# bldcshield.net
KiCad netlist of a schematic drawn in EAGLE
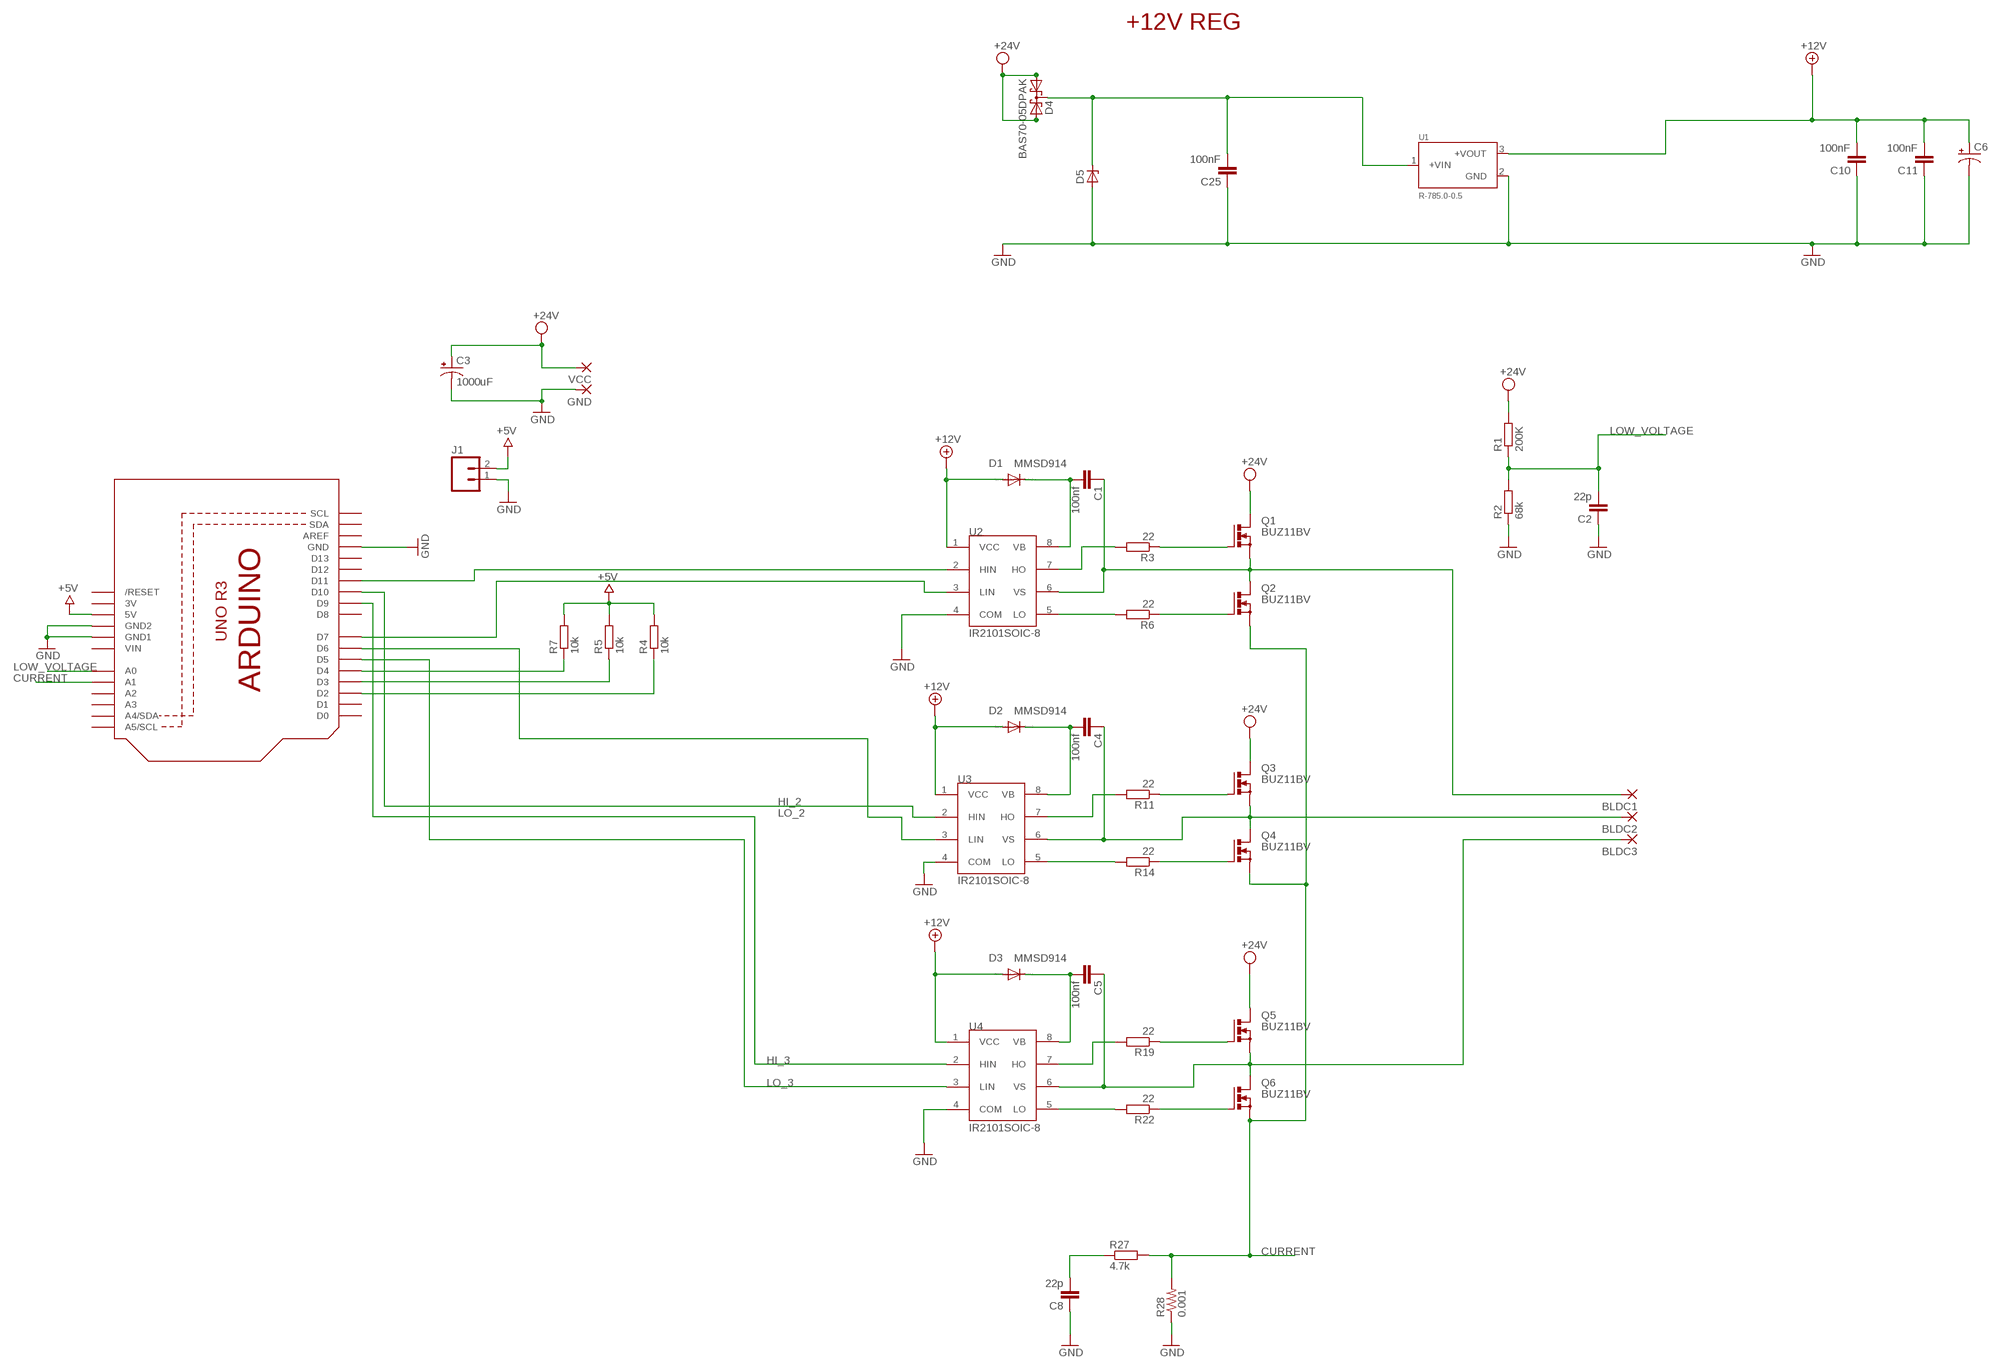
[diagram p0: schematic, sheet 1]

(export (version "E")
  (design (tool "Eeschema 10.0.6"))
  (components
    (comp (ref "BLDC1")
      (value "WIREPAD4,16O1,6")
      (footprint "eagle-import:4,16O1,6")
      (libsource (lib "eagle-import") (part "WIREPAD4,16O1,6"))
    )
    (comp (ref "BLDC2")
      (value "WIREPAD4,16O1,6")
      (footprint "eagle-import:4,16O1,6")
      (libsource (lib "eagle-import") (part "WIREPAD4,16O1,6"))
    )
    (comp (ref "BLDC3")
      (value "WIREPAD4,16O1,6")
      (footprint "eagle-import:4,16O1,6")
      (libsource (lib "eagle-import") (part "WIREPAD4,16O1,6"))
    )
    (comp (ref "C1")
      (value "100nf")
      (footprint "eagle-import:C1206")
      (libsource (lib "eagle-import") (part "C-EUC1206"))
    )
    (comp (ref "C2")
      (value "22p")
      (footprint "eagle-import:C1206")
      (libsource (lib "eagle-import") (part "C-EUC1206"))
    )
    (comp (ref "C3")
      (value "1000uF")
      (footprint "eagle-import:CPOL-RADIAL-1000UF-63V")
      (libsource (lib "eagle-import") (part "SparkFun-Passives_CAP_POLPTH3"))
    )
    (comp (ref "C4")
      (value "100nf")
      (footprint "eagle-import:C1206")
      (libsource (lib "eagle-import") (part "C-EUC1206"))
    )
    (comp (ref "C5")
      (value "100nf")
      (footprint "eagle-import:C1206")
      (libsource (lib "eagle-import") (part "C-EUC1206"))
    )
    (comp (ref "C6")
      (value "CAP_POLPTH1")
      (footprint "eagle-import:CPOL-RADIAL-100UF-25V")
      (libsource (lib "eagle-import") (part "CAP_POLPTH1"))
    )
    (comp (ref "C8")
      (value "22p")
      (footprint "eagle-import:C1206")
      (libsource (lib "eagle-import") (part "C-EUC1206"))
    )
    (comp (ref "C10")
      (value "100nF")
      (footprint "eagle-import:C1206")
      (libsource (lib "eagle-import") (part "C-EUC1206"))
    )
    (comp (ref "C11")
      (value "100nF")
      (footprint "eagle-import:C1206")
      (libsource (lib "eagle-import") (part "C-EUC1206"))
    )
    (comp (ref "C25")
      (value "100nF")
      (footprint "eagle-import:C1206")
      (libsource (lib "eagle-import") (part "C-EUC1206"))
    )
    (comp (ref "D1")
      (value "MMSD914")
      (footprint "eagle-import:SOD123")
      (libsource (lib "eagle-import") (part "DIODE-SOD123"))
    )
    (comp (ref "D2")
      (value "MMSD914")
      (footprint "eagle-import:SOD123")
      (libsource (lib "eagle-import") (part "DIODE-SOD123"))
    )
    (comp (ref "D3")
      (value "MMSD914")
      (footprint "eagle-import:SOD123")
      (libsource (lib "eagle-import") (part "DIODE-SOD123"))
    )
    (comp (ref "D4")
      (value "BAS70-05DPAK")
      (footprint "eagle-import:DPAK229P990X238-3N")
      (libsource (lib "eagle-import") (part "BAS70-05DPAK"))
    )
    (comp (ref "D5")
      (value "SMF43A")
      (footprint "eagle-import:SOD123F")
      (fields (field (name "MF") "Littelfuse"))
      (libsource (lib "eagle-import") (part "SMFA43"))
    )
    (comp (ref "GND")
      (value "WIREPAD4,16O1,6")
      (footprint "eagle-import:4,16O1,6")
      (libsource (lib "eagle-import") (part "WIREPAD4,16O1,6"))
    )
    (comp (ref "J1")
      (value "M02PTH")
      (footprint "eagle-import:1X02")
      (libsource (lib "eagle-import") (part "M02PTH"))
    )
    (comp (ref "Q1")
      (value "BUZ11BV")
      (footprint "eagle-import:TO220BV")
      (libsource (lib "eagle-import") (part "BUZ11BV"))
    )
    (comp (ref "Q2")
      (value "BUZ11BV")
      (footprint "eagle-import:TO220BV")
      (libsource (lib "eagle-import") (part "BUZ11BV"))
    )
    (comp (ref "Q3")
      (value "BUZ11BV")
      (footprint "eagle-import:TO220BV")
      (libsource (lib "eagle-import") (part "BUZ11BV"))
    )
    (comp (ref "Q4")
      (value "BUZ11BV")
      (footprint "eagle-import:TO220BV")
      (libsource (lib "eagle-import") (part "BUZ11BV"))
    )
    (comp (ref "Q5")
      (value "BUZ11BV")
      (footprint "eagle-import:TO220BV")
      (libsource (lib "eagle-import") (part "BUZ11BV"))
    )
    (comp (ref "Q6")
      (value "BUZ11BV")
      (footprint "eagle-import:TO220BV")
      (libsource (lib "eagle-import") (part "BUZ11BV"))
    )
    (comp (ref "Q8")
      (value "Shield")
      (footprint "eagle-import:ARDUINOR3-NOTEXT-NOIOREF")
      (libsource (lib "eagle-import") (part "ARDUINOR3-NOIOREF-NOTEXT"))
    )
    (comp (ref "R1")
      (value "200K")
      (footprint "eagle-import:R1206")
      (libsource (lib "eagle-import") (part "R-EU_R1206"))
    )
    (comp (ref "R2")
      (value "68k")
      (footprint "eagle-import:R1206")
      (libsource (lib "eagle-import") (part "R-EU_R1206"))
    )
    (comp (ref "R3")
      (value "22")
      (footprint "eagle-import:R1206")
      (libsource (lib "eagle-import") (part "R-EU_R1206"))
    )
    (comp (ref "R4")
      (value "10k")
      (footprint "eagle-import:R1206")
      (libsource (lib "eagle-import") (part "R-EU_R1206"))
    )
    (comp (ref "R5")
      (value "10k")
      (footprint "eagle-import:R1206")
      (libsource (lib "eagle-import") (part "R-EU_R1206"))
    )
    (comp (ref "R6")
      (value "22")
      (footprint "eagle-import:R1206")
      (libsource (lib "eagle-import") (part "R-EU_R1206"))
    )
    (comp (ref "R7")
      (value "10k")
      (footprint "eagle-import:R1206")
      (libsource (lib "eagle-import") (part "R-EU_R1206"))
    )
    (comp (ref "R11")
      (value "22")
      (footprint "eagle-import:R1206")
      (libsource (lib "eagle-import") (part "R-EU_R1206"))
    )
    (comp (ref "R14")
      (value "22")
      (footprint "eagle-import:R1206")
      (libsource (lib "eagle-import") (part "R-EU_R1206"))
    )
    (comp (ref "R19")
      (value "22")
      (footprint "eagle-import:R1206")
      (libsource (lib "eagle-import") (part "R-EU_R1206"))
    )
    (comp (ref "R22")
      (value "22")
      (footprint "eagle-import:R1206")
      (libsource (lib "eagle-import") (part "R-EU_R1206"))
    )
    (comp (ref "R27")
      (value "4.7k")
      (footprint "eagle-import:R1206")
      (libsource (lib "eagle-import") (part "R-EU_R1206"))
    )
    (comp (ref "R28")
      (value "0.001")
      (footprint "eagle-import:R2512")
      (libsource (lib "eagle-import") (part "R-US_R2512"))
    )
    (comp (ref "U1")
      (value "R-785.0-0.5")
      (footprint "eagle-import:RECOM_R-785.0-0.5")
      (fields (field (name "MF") "Recom Power"))
      (libsource (lib "eagle-import") (part "R-785.0-0.5"))
    )
    (comp (ref "U2")
      (value "IR2101SOIC-8")
      (footprint "eagle-import:SOIC127P490X600X175-8N")
      (libsource (lib "eagle-import") (part "IR2101SOIC-8"))
    )
    (comp (ref "U3")
      (value "IR2101SOIC-8")
      (footprint "eagle-import:SOIC127P490X600X175-8N")
      (libsource (lib "eagle-import") (part "IR2101SOIC-8"))
    )
    (comp (ref "U4")
      (value "IR2101SOIC-8")
      (footprint "eagle-import:SOIC127P490X600X175-8N")
      (libsource (lib "eagle-import") (part "IR2101SOIC-8"))
    )
    (comp (ref "VCC")
      (value "WIREPAD4,16O1,6")
      (footprint "eagle-import:4,16O1,6")
      (libsource (lib "eagle-import") (part "WIREPAD4,16O1,6"))
    )
  )
  (nets
    (net (code "1") (name "+5V") (class "Default")
      (node (ref "J1") (pin "2") (pinfunction "2_2") (pintype "passive"))
      (node (ref "Q8") (pin "5V") (pinfunction "5V_5V") (pintype "power_in"))
      (node (ref "R4") (pin "2") (pinfunction "2_2") (pintype "passive"))
      (node (ref "R5") (pin "2") (pinfunction "2_2") (pintype "passive"))
      (node (ref "R7") (pin "2") (pinfunction "2_2") (pintype "passive"))
    )
    (net (code "2") (name "+12V") (class "Default")
      (node (ref "C10") (pin "2") (pinfunction "2_2") (pintype "passive"))
      (node (ref "C11") (pin "2") (pinfunction "2_2") (pintype "passive"))
      (node (ref "C6") (pin "1") (pinfunction "+_1") (pintype "passive"))
      (node (ref "D1") (pin "A") (pinfunction "A_A") (pintype "passive"))
      (node (ref "D2") (pin "A") (pinfunction "A_A") (pintype "passive"))
      (node (ref "D3") (pin "A") (pinfunction "A_A") (pintype "passive"))
      (node (ref "U1") (pin "3") (pinfunction "+VOUT_3") (pintype "output"))
      (node (ref "U2") (pin "1") (pinfunction "VCC_1") (pintype "power_in"))
      (node (ref "U3") (pin "1") (pinfunction "VCC_1") (pintype "power_in"))
      (node (ref "U4") (pin "1") (pinfunction "VCC_1") (pintype "power_in"))
    )
    (net (code "3") (name "+24V") (class "Default")
      (node (ref "C3") (pin "1") (pinfunction "+_1") (pintype "passive"))
      (node (ref "D4") (pin "1") (pinfunction "A1_1") (pintype "passive"))
      (node (ref "D4") (pin "3") (pinfunction "A2_3") (pintype "passive"))
      (node (ref "Q1") (pin "D") (pinfunction "D_D") (pintype "passive"))
      (node (ref "Q3") (pin "D") (pinfunction "D_D") (pintype "passive"))
      (node (ref "Q5") (pin "D") (pinfunction "D_D") (pintype "passive"))
      (node (ref "R1") (pin "2") (pinfunction "2_2") (pintype "passive"))
      (node (ref "VCC") (pin "1") (pinfunction "P_1") (pintype "passive"))
    )
    (net (code "4") (name "/3V") (class "Default")
      (node (ref "Q8") (pin "3V") (pinfunction "3V_3V") (pintype "power_in"))
    )
    (net (code "5") (name "/CURRENT") (class "Default")
      (node (ref "Q2") (pin "S") (pinfunction "S_S") (pintype "passive"))
      (node (ref "Q4") (pin "S") (pinfunction "S_S") (pintype "passive"))
      (node (ref "Q6") (pin "S") (pinfunction "S_S") (pintype "passive"))
      (node (ref "Q8") (pin "A1") (pinfunction "A1_A1") (pintype "bidirectional"))
      (node (ref "R27") (pin "2") (pinfunction "2_2") (pintype "passive"))
      (node (ref "R28") (pin "2") (pinfunction "2_2") (pintype "passive"))
    )
    (net (code "6") (name "/HI_2") (class "Default")
      (node (ref "Q8") (pin "D10") (pinfunction "D10_D10") (pintype "bidirectional"))
      (node (ref "U3") (pin "2") (pinfunction "HIN_2") (pintype "input"))
    )
    (net (code "7") (name "/HI_3") (class "Default")
      (node (ref "Q8") (pin "D9") (pinfunction "D9_D9") (pintype "bidirectional"))
      (node (ref "U4") (pin "2") (pinfunction "HIN_2") (pintype "input"))
    )
    (net (code "8") (name "/LOW_VOLTAGE") (class "Default")
      (node (ref "C2") (pin "2") (pinfunction "2_2") (pintype "passive"))
      (node (ref "Q8") (pin "A0") (pinfunction "A0_A0") (pintype "bidirectional"))
      (node (ref "R1") (pin "1") (pinfunction "1_1") (pintype "passive"))
      (node (ref "R2") (pin "2") (pinfunction "2_2") (pintype "passive"))
    )
    (net (code "9") (name "/LO_2") (class "Default")
      (node (ref "Q8") (pin "D6") (pinfunction "D6_D6") (pintype "bidirectional"))
      (node (ref "U3") (pin "3") (pinfunction "LIN_3") (pintype "input"))
    )
    (net (code "10") (name "/LO_3") (class "Default")
      (node (ref "Q8") (pin "D5") (pinfunction "D5_D5") (pintype "bidirectional"))
      (node (ref "U4") (pin "3") (pinfunction "LIN_3") (pintype "input"))
    )
    (net (code "11") (name "/VIN") (class "Default")
      (node (ref "Q8") (pin "VIN") (pinfunction "VIN_VIN") (pintype "power_in"))
    )
    (net (code "12") (name "GND") (class "Default")
      (node (ref "C10") (pin "1") (pinfunction "1_1") (pintype "passive"))
      (node (ref "C11") (pin "1") (pinfunction "1_1") (pintype "passive"))
      (node (ref "C2") (pin "1") (pinfunction "1_1") (pintype "passive"))
      (node (ref "C25") (pin "1") (pinfunction "1_1") (pintype "passive"))
      (node (ref "C3") (pin "2") (pinfunction "-_2") (pintype "passive"))
      (node (ref "C6") (pin "2") (pinfunction "-_2") (pintype "passive"))
      (node (ref "C8") (pin "1") (pinfunction "1_1") (pintype "passive"))
      (node (ref "D5") (pin "A") (pinfunction "A_A") (pintype "passive"))
      (node (ref "GND") (pin "1") (pinfunction "P_1") (pintype "passive"))
      (node (ref "J1") (pin "1") (pinfunction "1_1") (pintype "passive"))
      (node (ref "Q8") (pin "GND") (pinfunction "GND_GND") (pintype "power_in"))
      (node (ref "Q8") (pin "GND1") (pinfunction "GND1_GND1") (pintype "power_in"))
      (node (ref "Q8") (pin "GND2") (pinfunction "GND2_GND2") (pintype "power_in"))
      (node (ref "R2") (pin "1") (pinfunction "1_1") (pintype "passive"))
      (node (ref "R28") (pin "1") (pinfunction "1_1") (pintype "passive"))
      (node (ref "U1") (pin "2") (pinfunction "GND_2") (pintype "power_in"))
      (node (ref "U2") (pin "4") (pinfunction "COM_4") (pintype "power_in"))
      (node (ref "U3") (pin "4") (pinfunction "COM_4") (pintype "power_in"))
      (node (ref "U4") (pin "4") (pinfunction "COM_4") (pintype "power_in"))
    )
    (net (code "13") (name "Net-(BLDC1-P)") (class "Default")
      (node (ref "BLDC1") (pin "1") (pinfunction "P_1") (pintype "passive"))
      (node (ref "C1") (pin "1") (pinfunction "1_1") (pintype "passive"))
      (node (ref "Q1") (pin "S") (pinfunction "S_S") (pintype "passive"))
      (node (ref "Q2") (pin "D") (pinfunction "D_D") (pintype "passive"))
      (node (ref "U2") (pin "6") (pinfunction "VS_6") (pintype "output"))
    )
    (net (code "14") (name "Net-(BLDC2-P)") (class "Default")
      (node (ref "BLDC2") (pin "1") (pinfunction "P_1") (pintype "passive"))
      (node (ref "C4") (pin "1") (pinfunction "1_1") (pintype "passive"))
      (node (ref "Q3") (pin "S") (pinfunction "S_S") (pintype "passive"))
      (node (ref "Q4") (pin "D") (pinfunction "D_D") (pintype "passive"))
      (node (ref "U3") (pin "6") (pinfunction "VS_6") (pintype "output"))
    )
    (net (code "15") (name "Net-(BLDC3-P)") (class "Default")
      (node (ref "BLDC3") (pin "1") (pinfunction "P_1") (pintype "passive"))
      (node (ref "C5") (pin "1") (pinfunction "1_1") (pintype "passive"))
      (node (ref "Q5") (pin "S") (pinfunction "S_S") (pintype "passive"))
      (node (ref "Q6") (pin "D") (pinfunction "D_D") (pintype "passive"))
      (node (ref "U4") (pin "6") (pinfunction "VS_6") (pintype "output"))
    )
    (net (code "16") (name "Net-(C8-Pad2)") (class "Default")
      (node (ref "C8") (pin "2") (pinfunction "2_2") (pintype "passive"))
      (node (ref "R27") (pin "1") (pinfunction "1_1") (pintype "passive"))
    )
    (net (code "17") (name "Net-(D4-K1K2)") (class "Default")
      (node (ref "C25") (pin "2") (pinfunction "2_2") (pintype "passive"))
      (node (ref "D4") (pin "4") (pinfunction "K1K2_4") (pintype "passive"))
      (node (ref "D5") (pin "C") (pinfunction "C_C") (pintype "passive"))
      (node (ref "U1") (pin "1") (pinfunction "+VIN_1") (pintype "input"))
    )
    (net (code "18") (name "Net-(Q1-PadG)") (class "Default")
      (node (ref "Q1") (pin "G") (pinfunction "G_G") (pintype "passive"))
      (node (ref "R3") (pin "1") (pinfunction "1_1") (pintype "passive"))
    )
    (net (code "19") (name "Net-(Q2-PadG)") (class "Default")
      (node (ref "Q2") (pin "G") (pinfunction "G_G") (pintype "passive"))
      (node (ref "R6") (pin "1") (pinfunction "1_1") (pintype "passive"))
    )
    (net (code "20") (name "Net-(Q3-PadG)") (class "Default")
      (node (ref "Q3") (pin "G") (pinfunction "G_G") (pintype "passive"))
      (node (ref "R11") (pin "1") (pinfunction "1_1") (pintype "passive"))
    )
    (net (code "21") (name "Net-(Q4-PadG)") (class "Default")
      (node (ref "Q4") (pin "G") (pinfunction "G_G") (pintype "passive"))
      (node (ref "R14") (pin "1") (pinfunction "1_1") (pintype "passive"))
    )
    (net (code "22") (name "Net-(Q5-PadG)") (class "Default")
      (node (ref "Q5") (pin "G") (pinfunction "G_G") (pintype "passive"))
      (node (ref "R19") (pin "1") (pinfunction "1_1") (pintype "passive"))
    )
    (net (code "23") (name "Net-(Q6-PadG)") (class "Default")
      (node (ref "Q6") (pin "G") (pinfunction "G_G") (pintype "passive"))
      (node (ref "R22") (pin "1") (pinfunction "1_1") (pintype "passive"))
    )
    (net (code "24") (name "Net-(Q8-PadD2)") (class "Default")
      (node (ref "Q8") (pin "D2") (pinfunction "D2_D2") (pintype "bidirectional"))
      (node (ref "R4") (pin "1") (pinfunction "1_1") (pintype "passive"))
    )
    (net (code "25") (name "Net-(Q8-PadD3)") (class "Default")
      (node (ref "Q8") (pin "D3") (pinfunction "D3_D3") (pintype "bidirectional"))
      (node (ref "R5") (pin "1") (pinfunction "1_1") (pintype "passive"))
    )
    (net (code "26") (name "Net-(Q8-PadD4)") (class "Default")
      (node (ref "Q8") (pin "D4") (pinfunction "D4_D4") (pintype "bidirectional"))
      (node (ref "R7") (pin "1") (pinfunction "1_1") (pintype "passive"))
    )
    (net (code "27") (name "Net-(U2-HIN)") (class "Default")
      (node (ref "Q8") (pin "D11") (pinfunction "D11_D11") (pintype "bidirectional"))
      (node (ref "U2") (pin "2") (pinfunction "HIN_2") (pintype "input"))
    )
    (net (code "28") (name "Net-(U2-HO)") (class "Default")
      (node (ref "R3") (pin "2") (pinfunction "2_2") (pintype "passive"))
      (node (ref "U2") (pin "7") (pinfunction "HO_7") (pintype "output"))
    )
    (net (code "29") (name "Net-(U2-LIN)") (class "Default")
      (node (ref "Q8") (pin "D7") (pinfunction "D7_D7") (pintype "bidirectional"))
      (node (ref "U2") (pin "3") (pinfunction "LIN_3") (pintype "input"))
    )
    (net (code "30") (name "Net-(U2-LO)") (class "Default")
      (node (ref "R6") (pin "2") (pinfunction "2_2") (pintype "passive"))
      (node (ref "U2") (pin "5") (pinfunction "LO_5") (pintype "output"))
    )
    (net (code "31") (name "Net-(U2-VB)") (class "Default")
      (node (ref "C1") (pin "2") (pinfunction "2_2") (pintype "passive"))
      (node (ref "D1") (pin "C") (pinfunction "C_C") (pintype "passive"))
      (node (ref "U2") (pin "8") (pinfunction "VB_8") (pintype "power_in"))
    )
    (net (code "32") (name "Net-(U3-HO)") (class "Default")
      (node (ref "R11") (pin "2") (pinfunction "2_2") (pintype "passive"))
      (node (ref "U3") (pin "7") (pinfunction "HO_7") (pintype "output"))
    )
    (net (code "33") (name "Net-(U3-LO)") (class "Default")
      (node (ref "R14") (pin "2") (pinfunction "2_2") (pintype "passive"))
      (node (ref "U3") (pin "5") (pinfunction "LO_5") (pintype "output"))
    )
    (net (code "34") (name "Net-(U3-VB)") (class "Default")
      (node (ref "C4") (pin "2") (pinfunction "2_2") (pintype "passive"))
      (node (ref "D2") (pin "C") (pinfunction "C_C") (pintype "passive"))
      (node (ref "U3") (pin "8") (pinfunction "VB_8") (pintype "power_in"))
    )
    (net (code "35") (name "Net-(U4-HO)") (class "Default")
      (node (ref "R19") (pin "2") (pinfunction "2_2") (pintype "passive"))
      (node (ref "U4") (pin "7") (pinfunction "HO_7") (pintype "output"))
    )
    (net (code "36") (name "Net-(U4-LO)") (class "Default")
      (node (ref "R22") (pin "2") (pinfunction "2_2") (pintype "passive"))
      (node (ref "U4") (pin "5") (pinfunction "LO_5") (pintype "output"))
    )
    (net (code "37") (name "Net-(U4-VB)") (class "Default")
      (node (ref "C5") (pin "2") (pinfunction "2_2") (pintype "passive"))
      (node (ref "D3") (pin "C") (pinfunction "C_C") (pintype "passive"))
      (node (ref "U4") (pin "8") (pinfunction "VB_8") (pintype "power_in"))
    )
    (net (code "38") (name "unconnected-(Q8-A4{slash}SDA-PadA4)") (class "Default")
      (node (ref "Q8") (pin "A4") (pinfunction "A4/SDA_A4") (pintype "bidirectional"))
    )
    (net (code "39") (name "unconnected-(Q8-A5{slash}SCL-PadA5)") (class "Default")
      (node (ref "Q8") (pin "A5") (pinfunction "A5/SCL_A5") (pintype "bidirectional"))
    )
    (net (code "40") (name "unconnected-(Q8-PadA2)") (class "Default")
      (node (ref "Q8") (pin "A2") (pinfunction "A2_A2") (pintype "bidirectional"))
    )
    (net (code "41") (name "unconnected-(Q8-PadA3)") (class "Default")
      (node (ref "Q8") (pin "A3") (pinfunction "A3_A3") (pintype "bidirectional"))
    )
    (net (code "42") (name "unconnected-(Q8-PadAREF)") (class "Default")
      (node (ref "Q8") (pin "AREF") (pinfunction "AREF_AREF") (pintype "bidirectional"))
    )
    (net (code "43") (name "unconnected-(Q8-PadD0)") (class "Default")
      (node (ref "Q8") (pin "D0") (pinfunction "D0_D0") (pintype "bidirectional"))
    )
    (net (code "44") (name "unconnected-(Q8-PadD1)") (class "Default")
      (node (ref "Q8") (pin "D1") (pinfunction "D1_D1") (pintype "bidirectional"))
    )
    (net (code "45") (name "unconnected-(Q8-PadD8)") (class "Default")
      (node (ref "Q8") (pin "D8") (pinfunction "D8_D8") (pintype "bidirectional"))
    )
    (net (code "46") (name "unconnected-(Q8-PadD12)") (class "Default")
      (node (ref "Q8") (pin "D12") (pinfunction "D12_D12") (pintype "bidirectional"))
    )
    (net (code "47") (name "unconnected-(Q8-PadD13)") (class "Default")
      (node (ref "Q8") (pin "D13") (pinfunction "D13_D13") (pintype "bidirectional"))
    )
    (net (code "48") (name "unconnected-(Q8-PadSCL)") (class "Default")
      (node (ref "Q8") (pin "SCL") (pinfunction "SCL_SCL") (pintype "bidirectional"))
    )
    (net (code "49") (name "unconnected-(Q8-PadSDA)") (class "Default")
      (node (ref "Q8") (pin "SDA") (pinfunction "SDA_SDA") (pintype "bidirectional"))
    )
    (net (code "50") (name "unconnected-(Q8-{slash}RESET-PadRESET)") (class "Default")
      (node (ref "Q8") (pin "RESET") (pinfunction "/RESET_RESET") (pintype "bidirectional"))
    )
  )
)
